# DAC.net
KiCad netlist of a schematic drawn in Altium Designer
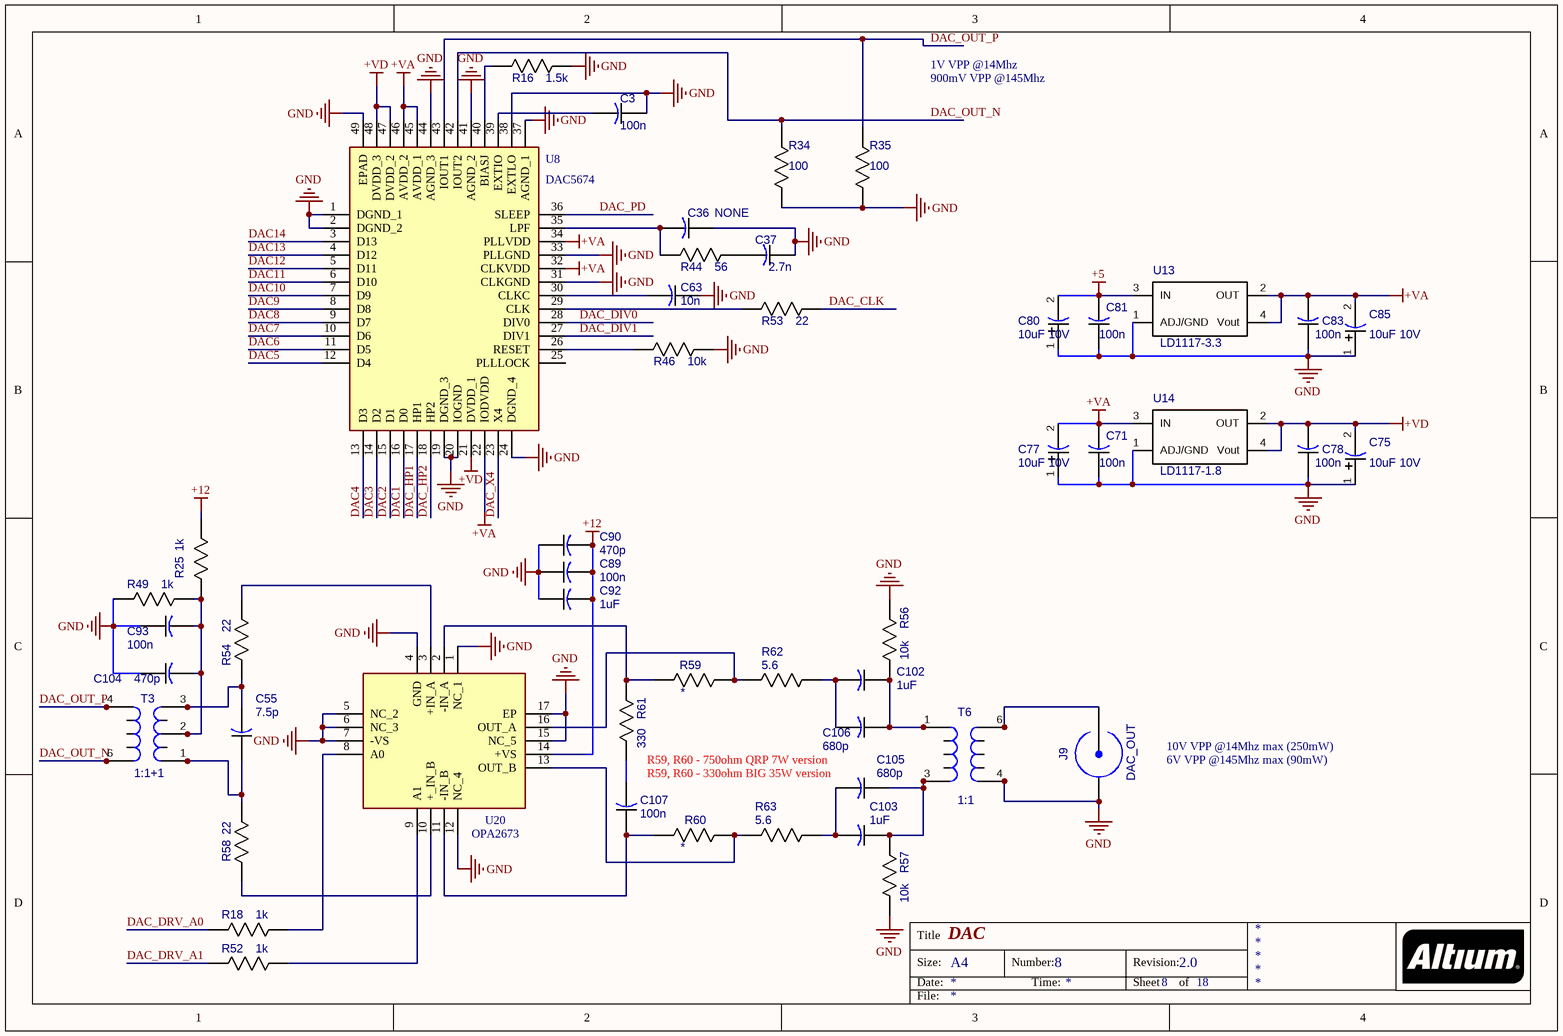
[diagram p0: DAC.SchDoc]

(export (version "E")
  (design (tool "Eeschema 10.0.6"))
  (components
    (comp (ref "C3")
      (value "100n")
      (footprint "CAP_0805")
      (description "CAP_0805")
      (libsource (lib "*") (part "CAP_0805"))
    )
    (comp (ref "C36")
      (value "NONE")
      (footprint "CAP_0805")
      (description "CAP_0805")
      (libsource (lib "*") (part "CAP_0805"))
    )
    (comp (ref "C37")
      (value "2.7n")
      (footprint "CAP_0805")
      (description "CAP_0805")
      (libsource (lib "*") (part "CAP_0805"))
    )
    (comp (ref "C55")
      (value "7.5p")
      (footprint "CAP_0805")
      (description "CAP_0805")
      (libsource (lib "*") (part "CAP_0805"))
    )
    (comp (ref "C63")
      (value "10n")
      (footprint "CAP_0805")
      (description "CAP_0805")
      (libsource (lib "*") (part "CAP_0805"))
    )
    (comp (ref "C71")
      (value "100n")
      (footprint "CAP_0805")
      (description "CAP_0805")
      (libsource (lib "*") (part "CAP_0805"))
    )
    (comp (ref "C75")
      (value "10uF 10V")
      (footprint "CAPAE_4.3x4.3h5.4")
      (description "CAPAE_4.3x4.3h5.4")
      (libsource (lib "MOTHERBOARD") (part "CAPAE_4.3x4.3h5.4"))
    )
    (comp (ref "C77")
      (value "10uF 10V")
      (footprint "CAPAE_4.3x4.3h5.4")
      (description "CAPAE_4.3x4.3h5.4")
      (libsource (lib "MOTHERBOARD") (part "CAPAE_4.3x4.3h5.4"))
    )
    (comp (ref "C78")
      (value "100n")
      (footprint "CAP_0805")
      (description "CAP_0805")
      (libsource (lib "*") (part "CAP_0805"))
    )
    (comp (ref "C80")
      (value "10uF 10V")
      (footprint "CAPAE_4.3x4.3h5.4")
      (description "CAPAE_4.3x4.3h5.4")
      (libsource (lib "MOTHERBOARD") (part "CAPAE_4.3x4.3h5.4"))
    )
    (comp (ref "C81")
      (value "100n")
      (footprint "CAP_0805")
      (description "CAP_0805")
      (libsource (lib "*") (part "CAP_0805"))
    )
    (comp (ref "C83")
      (value "100n")
      (footprint "CAP_0805")
      (description "CAP_0805")
      (libsource (lib "*") (part "CAP_0805"))
    )
    (comp (ref "C85")
      (value "10uF 10V")
      (footprint "CAPAE_4.3x4.3h5.4")
      (description "CAPAE_4.3x4.3h5.4")
      (libsource (lib "MOTHERBOARD") (part "CAPAE_4.3x4.3h5.4"))
    )
    (comp (ref "C89")
      (value "100n")
      (footprint "CAP_0805")
      (description "CAP_0805")
      (libsource (lib "*") (part "CAP_0805"))
    )
    (comp (ref "C90")
      (value "470p")
      (footprint "CAP_0805")
      (description "CAP_0805")
      (libsource (lib "*") (part "CAP_0805"))
    )
    (comp (ref "C92")
      (value "1uF")
      (footprint "CAP_0805")
      (description "CAP_0805")
      (libsource (lib "*") (part "CAP_0805"))
    )
    (comp (ref "C93")
      (value "100n")
      (footprint "CAP_0805")
      (description "CAP_0805")
      (libsource (lib "*") (part "CAP_0805"))
    )
    (comp (ref "C102")
      (value "1uF")
      (footprint "CAP_1206")
      (description "CAP_1206")
      (libsource (lib "*") (part "CAP_1206"))
    )
    (comp (ref "C103")
      (value "1uF")
      (footprint "CAP_1206")
      (description "CAP_1206")
      (libsource (lib "*") (part "CAP_1206"))
    )
    (comp (ref "C104")
      (value "470p")
      (footprint "CAP_0805")
      (description "CAP_0805")
      (libsource (lib "*") (part "CAP_0805"))
    )
    (comp (ref "C105")
      (value "680p")
      (footprint "CAP_1206")
      (description "CAP_1206")
      (libsource (lib "*") (part "CAP_1206"))
    )
    (comp (ref "C106")
      (value "680p")
      (footprint "CAP_1206")
      (description "CAP_1206")
      (libsource (lib "*") (part "CAP_1206"))
    )
    (comp (ref "C107")
      (value "100n")
      (footprint "CAP_0805")
      (description "CAP_0805")
      (libsource (lib "*") (part "CAP_0805"))
    )
    (comp (ref "J9")
      (value "DAC_OUT")
      (footprint "31-5431")
      (description "SMA")
      (libsource (lib "RF-UNIT_1") (part "31-5431"))
    )
    (comp (ref "R16")
      (value "1.5k")
      (footprint "RES_0805")
      (description "RES_0805")
      (libsource (lib "*") (part "RES_0805"))
    )
    (comp (ref "R18")
      (value "1k")
      (footprint "RES_0805")
      (description "RES_0805")
      (libsource (lib "*") (part "RES_0805"))
    )
    (comp (ref "R25")
      (value "1k")
      (footprint "RES_0805")
      (description "RES_0805")
      (libsource (lib "*") (part "RES_0805"))
    )
    (comp (ref "R34")
      (value "100")
      (footprint "RES_0805")
      (description "RES_0805")
      (libsource (lib "*") (part "RES_0805"))
    )
    (comp (ref "R35")
      (value "100")
      (footprint "RES_0805")
      (description "RES_0805")
      (libsource (lib "*") (part "RES_0805"))
    )
    (comp (ref "R44")
      (value "56")
      (footprint "RES_0805")
      (description "RES_0805")
      (libsource (lib "*") (part "RES_0805"))
    )
    (comp (ref "R46")
      (value "10k")
      (footprint "RES_0805")
      (description "RES_0805")
      (libsource (lib "*") (part "RES_0805"))
    )
    (comp (ref "R49")
      (value "1k")
      (footprint "RES_0805")
      (description "RES_0805")
      (libsource (lib "*") (part "RES_0805"))
    )
    (comp (ref "R52")
      (value "1k")
      (footprint "RES_0805")
      (description "RES_0805")
      (libsource (lib "*") (part "RES_0805"))
    )
    (comp (ref "R53")
      (value "22")
      (footprint "RES_0805")
      (description "RES_0805")
      (libsource (lib "*") (part "RES_0805"))
    )
    (comp (ref "R54")
      (value "22")
      (footprint "RES_0805")
      (description "RES_0805")
      (libsource (lib "*") (part "RES_0805"))
    )
    (comp (ref "R56")
      (value "10k")
      (footprint "RES_0805")
      (description "RES_0805")
      (libsource (lib "*") (part "RES_0805"))
    )
    (comp (ref "R57")
      (value "10k")
      (footprint "RES_0805")
      (description "RES_0805")
      (libsource (lib "*") (part "RES_0805"))
    )
    (comp (ref "R58")
      (value "22")
      (footprint "RES_0805")
      (description "RES_0805")
      (libsource (lib "*") (part "RES_0805"))
    )
    (comp (ref "R59")
      (value "*")
      (footprint "RES_0805")
      (description "RES_0805")
      (libsource (lib "*") (part "RES_0805"))
    )
    (comp (ref "R60")
      (value "*")
      (footprint "RES_0805")
      (description "RES_0805")
      (libsource (lib "*") (part "RES_0805"))
    )
    (comp (ref "R61")
      (value "330")
      (footprint "RES_0805")
      (description "RES_0805")
      (libsource (lib "*") (part "RES_0805"))
    )
    (comp (ref "R62")
      (value "5.6")
      (footprint "RES_1206")
      (description "RES_1206")
      (libsource (lib "*") (part "RES_1206"))
    )
    (comp (ref "R63")
      (value "5.6")
      (footprint "RES_1206")
      (description "RES_1206")
      (libsource (lib "*") (part "RES_1206"))
    )
    (comp (ref "T3")
      (value "1:1+1")
      (footprint "TRANSF_ACORE2")
      (description "Transformer")
      (libsource (lib "MOTHERBOARD_1") (part "TRANSF_ACORE2"))
    )
    (comp (ref "T6")
      (value "1:1")
      (footprint "TRANSF_ACORE")
      (description "Transformer")
      (libsource (lib "MOTHERBOARD_1") (part "TRANSF_ACORE"))
    )
    (comp (ref "U8")
      (value "DAC5674")
      (footprint "SamacSys:QFP50P900X900X100-49N")
      (description "Integrated Circuit")
      (fields (field (name "MANUFACTURER_PART_NUMBER") "DAC5674IPHP"))
      (libsource (lib "*") (part "DAC5674IPHP"))
    )
    (comp (ref "U13")
      (value "LD1117-3.3")
      (footprint "LT1117CST-3.3")
      (description "LT1117CST-3.3")
      (fields (field (name "Comment") "1117-3.3"))
      (libsource (lib "*") (part "LT1117CST-3.3"))
    )
    (comp (ref "U14")
      (value "LD1117-1.8")
      (footprint "LT1117CST-3.3")
      (description "LT1117CST-1.8")
      (fields (field (name "Comment") "1117-1.8"))
      (libsource (lib "*") (part "LT1117CST-3.3"))
    )
    (comp (ref "U20")
      (value "OPA2673")
      (footprint "SamacSys:QFN65P400X400X100-17N-D")
      (description "Integrated Circuit")
      (fields
        (field (name "MANUFACTURER_PART_NUMBER") "OPA2673IRGVT")
        (field (name "MOUSER PART NUMBER") "595-OPA2673IRGVT")
      )
      (libsource (lib "*") (part "OPA2673IRGVT"))
    )
  )
  (nets
    (net (code "1") (name "+5") (class "Default")
      (node (ref "C80") (pin "2") (pinfunction "MINUS_2") (pintype "passive"))
      (node (ref "C81") (pin "2") (pinfunction "2_2") (pintype "passive"))
      (node (ref "U13") (pin "3") (pinfunction "IN_3") (pintype "passive"))
    )
    (net (code "2") (name "+12") (class "Default")
      (node (ref "C89") (pin "2") (pinfunction "2_2") (pintype "passive"))
      (node (ref "C90") (pin "2") (pinfunction "2_2") (pintype "passive"))
      (node (ref "C92") (pin "2") (pinfunction "2_2") (pintype "passive"))
      (node (ref "R25") (pin "2") (pinfunction "2_2") (pintype "passive"))
      (node (ref "U20") (pin "14") (pinfunction "+VS_14") (pintype "passive"))
    )
    (net (code "3") (name "+VA") (class "Default")
      (node (ref "C71") (pin "2") (pinfunction "2_2") (pintype "passive"))
      (node (ref "C77") (pin "2") (pinfunction "MINUS_2") (pintype "passive"))
      (node (ref "C83") (pin "2") (pinfunction "2_2") (pintype "passive"))
      (node (ref "C85") (pin "2") (pinfunction "MINUS_2") (pintype "passive"))
      (node (ref "U13") (pin "2") (pinfunction "OUT_2") (pintype "passive"))
      (node (ref "U13") (pin "4") (pinfunction "Vout_4") (pintype "passive"))
      (node (ref "U14") (pin "3") (pinfunction "IN_3") (pintype "passive"))
      (node (ref "U8") (pin "22") (pinfunction "IODVDD_22") (pintype "passive"))
      (node (ref "U8") (pin "32") (pinfunction "CLKVDD_32") (pintype "passive"))
      (node (ref "U8") (pin "34") (pinfunction "PLLVDD_34") (pintype "passive"))
      (node (ref "U8") (pin "45") (pinfunction "AVDD_1_45") (pintype "passive"))
      (node (ref "U8") (pin "46") (pinfunction "AVDD_2_46") (pintype "passive"))
    )
    (net (code "4") (name "+VD") (class "Default")
      (node (ref "C75") (pin "2") (pinfunction "MINUS_2") (pintype "passive"))
      (node (ref "C78") (pin "2") (pinfunction "2_2") (pintype "passive"))
      (node (ref "U14") (pin "2") (pinfunction "OUT_2") (pintype "passive"))
      (node (ref "U14") (pin "4") (pinfunction "Vout_4") (pintype "passive"))
      (node (ref "U8") (pin "21") (pinfunction "DVDD_1_21") (pintype "passive"))
      (node (ref "U8") (pin "47") (pinfunction "DVDD_2_47") (pintype "passive"))
      (node (ref "U8") (pin "48") (pinfunction "DVDD_3_48") (pintype "passive"))
    )
    (net (code "5") (name "/DAC1") (class "Default")
      (node (ref "U8") (pin "16") (pinfunction "D0_16") (pintype "passive"))
    )
    (net (code "6") (name "/DAC2") (class "Default")
      (node (ref "U8") (pin "15") (pinfunction "D1_15") (pintype "passive"))
    )
    (net (code "7") (name "/DAC3") (class "Default")
      (node (ref "U8") (pin "14") (pinfunction "D2_14") (pintype "passive"))
    )
    (net (code "8") (name "/DAC4") (class "Default")
      (node (ref "U8") (pin "13") (pinfunction "D3_13") (pintype "passive"))
    )
    (net (code "9") (name "/DAC5") (class "Default")
      (node (ref "U8") (pin "12") (pinfunction "D4_12") (pintype "passive"))
    )
    (net (code "10") (name "/DAC6") (class "Default")
      (node (ref "U8") (pin "11") (pinfunction "D5_11") (pintype "passive"))
    )
    (net (code "11") (name "/DAC7") (class "Default")
      (node (ref "U8") (pin "10") (pinfunction "D6_10") (pintype "passive"))
    )
    (net (code "12") (name "/DAC8") (class "Default")
      (node (ref "U8") (pin "9") (pinfunction "D7_9") (pintype "passive"))
    )
    (net (code "13") (name "/DAC9") (class "Default")
      (node (ref "U8") (pin "8") (pinfunction "D8_8") (pintype "passive"))
    )
    (net (code "14") (name "/DAC10") (class "Default")
      (node (ref "U8") (pin "7") (pinfunction "D9_7") (pintype "passive"))
    )
    (net (code "15") (name "/DAC11") (class "Default")
      (node (ref "U8") (pin "6") (pinfunction "D10_6") (pintype "passive"))
    )
    (net (code "16") (name "/DAC12") (class "Default")
      (node (ref "U8") (pin "5") (pinfunction "D11_5") (pintype "passive"))
    )
    (net (code "17") (name "/DAC13") (class "Default")
      (node (ref "U8") (pin "4") (pinfunction "D12_4") (pintype "passive"))
    )
    (net (code "18") (name "/DAC14") (class "Default")
      (node (ref "U8") (pin "3") (pinfunction "D13_3") (pintype "passive"))
    )
    (net (code "19") (name "/DAC_CLK") (class "Default")
      (node (ref "R53") (pin "1") (pinfunction "1_1") (pintype "passive"))
    )
    (net (code "20") (name "/DAC_DIV0") (class "Default")
      (node (ref "U8") (pin "28") (pinfunction "DIV0_28") (pintype "passive"))
    )
    (net (code "21") (name "/DAC_DIV1") (class "Default")
      (node (ref "U8") (pin "27") (pinfunction "DIV1_27") (pintype "passive"))
    )
    (net (code "22") (name "/DAC_DRV_A0") (class "Default")
      (node (ref "R18") (pin "1") (pinfunction "1_1") (pintype "passive"))
    )
    (net (code "23") (name "/DAC_DRV_A1") (class "Default")
      (node (ref "R52") (pin "1") (pinfunction "1_1") (pintype "passive"))
    )
    (net (code "24") (name "/DAC_HP1") (class "Default")
      (node (ref "U8") (pin "17") (pinfunction "HP1_17") (pintype "passive"))
    )
    (net (code "25") (name "/DAC_HP2") (class "Default")
      (node (ref "U8") (pin "18") (pinfunction "HP2_18") (pintype "passive"))
    )
    (net (code "26") (name "/DAC_OUT_N") (class "Default")
      (node (ref "R34") (pin "2") (pinfunction "2_2") (pintype "passive"))
      (node (ref "T3") (pin "10") (pinfunction "0_10") (pintype "passive"))
      (node (ref "T3") (pin "6") (pinfunction "P2_6") (pintype "passive"))
      (node (ref "U8") (pin "42") (pinfunction "IOUT2_42") (pintype "passive"))
    )
    (net (code "27") (name "/DAC_OUT_P") (class "Default")
      (node (ref "R35") (pin "2") (pinfunction "2_2") (pintype "passive"))
      (node (ref "T3") (pin "11") (pinfunction "0_11") (pintype "passive"))
      (node (ref "T3") (pin "4") (pinfunction "P1_4") (pintype "passive"))
      (node (ref "U8") (pin "43") (pinfunction "IOUT1_43") (pintype "passive"))
    )
    (net (code "28") (name "/DAC_PD") (class "Default")
      (node (ref "U8") (pin "36") (pinfunction "SLEEP_36") (pintype "passive"))
    )
    (net (code "29") (name "/DAC_X4") (class "Default")
      (node (ref "U8") (pin "23") (pinfunction "X4_23") (pintype "passive"))
    )
    (net (code "30") (name "GND") (class "Default")
      (node (ref "C104") (pin "1") (pinfunction "1_1") (pintype "passive"))
      (node (ref "C3") (pin "1") (pinfunction "1_1") (pintype "passive"))
      (node (ref "C36") (pin "1") (pinfunction "1_1") (pintype "passive"))
      (node (ref "C37") (pin "1") (pinfunction "1_1") (pintype "passive"))
      (node (ref "C63") (pin "1") (pinfunction "1_1") (pintype "passive"))
      (node (ref "C71") (pin "1") (pinfunction "1_1") (pintype "passive"))
      (node (ref "C75") (pin "1") (pinfunction "PLUS_1") (pintype "passive"))
      (node (ref "C77") (pin "1") (pinfunction "PLUS_1") (pintype "passive"))
      (node (ref "C78") (pin "1") (pinfunction "1_1") (pintype "passive"))
      (node (ref "C80") (pin "1") (pinfunction "PLUS_1") (pintype "passive"))
      (node (ref "C81") (pin "1") (pinfunction "1_1") (pintype "passive"))
      (node (ref "C83") (pin "1") (pinfunction "1_1") (pintype "passive"))
      (node (ref "C85") (pin "1") (pinfunction "PLUS_1") (pintype "passive"))
      (node (ref "C89") (pin "1") (pinfunction "1_1") (pintype "passive"))
      (node (ref "C90") (pin "1") (pinfunction "1_1") (pintype "passive"))
      (node (ref "C92") (pin "1") (pinfunction "1_1") (pintype "passive"))
      (node (ref "C93") (pin "1") (pinfunction "1_1") (pintype "passive"))
      (node (ref "J9") (pin "1") (pinfunction "GND_1") (pintype "passive"))
      (node (ref "J9") (pin "2") (pinfunction "GND_2") (pintype "passive"))
      (node (ref "J9") (pin "3") (pinfunction "GND_3") (pintype "passive"))
      (node (ref "J9") (pin "4") (pinfunction "GND_4") (pintype "passive"))
      (node (ref "R16") (pin "1") (pinfunction "1_1") (pintype "passive"))
      (node (ref "R34") (pin "1") (pinfunction "1_1") (pintype "passive"))
      (node (ref "R35") (pin "1") (pinfunction "1_1") (pintype "passive"))
      (node (ref "R46") (pin "1") (pinfunction "1_1") (pintype "passive"))
      (node (ref "R49") (pin "2") (pinfunction "2_2") (pintype "passive"))
      (node (ref "R56") (pin "1") (pinfunction "1_1") (pintype "passive"))
      (node (ref "R57") (pin "2") (pinfunction "2_2") (pintype "passive"))
      (node (ref "T6") (pin "11") (pinfunction "0_11") (pintype "passive"))
      (node (ref "T6") (pin "4") (pinfunction "S2_4") (pintype "passive"))
      (node (ref "U13") (pin "1") (pinfunction "ADJ/GND_1") (pintype "passive"))
      (node (ref "U14") (pin "1") (pinfunction "ADJ/GND_1") (pintype "passive"))
      (node (ref "U20") (pin "1") (pinfunction "NC_1_1") (pintype "passive"))
      (node (ref "U20") (pin "12") (pinfunction "NC_4_12") (pintype "passive"))
      (node (ref "U20") (pin "15") (pinfunction "NC_5_15") (pintype "passive"))
      (node (ref "U20") (pin "17") (pinfunction "EP_17") (pintype "passive"))
      (node (ref "U20") (pin "4") (pinfunction "GND_4") (pintype "passive"))
      (node (ref "U20") (pin "5") (pinfunction "NC_2_5") (pintype "passive"))
      (node (ref "U20") (pin "6") (pinfunction "NC_3_6") (pintype "passive"))
      (node (ref "U20") (pin "7") (pinfunction "-VS_7") (pintype "passive"))
      (node (ref "U8") (pin "1") (pinfunction "DGND_1_1") (pintype "passive"))
      (node (ref "U8") (pin "19") (pinfunction "DGND_3_19") (pintype "passive"))
      (node (ref "U8") (pin "2") (pinfunction "DGND_2_2") (pintype "passive"))
      (node (ref "U8") (pin "20") (pinfunction "IOGND_20") (pintype "passive"))
      (node (ref "U8") (pin "24") (pinfunction "DGND_4_24") (pintype "passive"))
      (node (ref "U8") (pin "31") (pinfunction "CLKGND_31") (pintype "passive"))
      (node (ref "U8") (pin "33") (pinfunction "PLLGND_33") (pintype "passive"))
      (node (ref "U8") (pin "37") (pinfunction "AGND_1_37") (pintype "passive"))
      (node (ref "U8") (pin "38") (pinfunction "EXTLO_38") (pintype "passive"))
      (node (ref "U8") (pin "41") (pinfunction "AGND_2_41") (pintype "passive"))
      (node (ref "U8") (pin "44") (pinfunction "AGND_3_44") (pintype "passive"))
      (node (ref "U8") (pin "49") (pinfunction "EPAD_49") (pintype "passive"))
    )
    (net (code "31") (name "Net-(C37-Pad2)") (class "Default")
      (node (ref "C37") (pin "2") (pinfunction "2_2") (pintype "passive"))
      (node (ref "R44") (pin "1") (pinfunction "1_1") (pintype "passive"))
    )
    (net (code "32") (name "Net-(C102-Pad2)") (class "Default")
      (node (ref "C102") (pin "2") (pinfunction "2_2") (pintype "passive"))
      (node (ref "C106") (pin "2") (pinfunction "2_2") (pintype "passive"))
      (node (ref "R62") (pin "1") (pinfunction "1_1") (pintype "passive"))
    )
    (net (code "33") (name "Net-(C103-Pad2)") (class "Default")
      (node (ref "C103") (pin "2") (pinfunction "2_2") (pintype "passive"))
      (node (ref "C105") (pin "2") (pinfunction "2_2") (pintype "passive"))
      (node (ref "R63") (pin "1") (pinfunction "1_1") (pintype "passive"))
    )
    (net (code "34") (name "Net-(C107-Pad2)") (class "Default")
      (node (ref "C107") (pin "2") (pinfunction "2_2") (pintype "passive"))
      (node (ref "R61") (pin "2") (pinfunction "2_2") (pintype "passive"))
    )
    (net (code "35") (name "Net-(J9-CON)") (class "Default")
      (node (ref "J9") (pin "5") (pinfunction "CON_5") (pintype "passive"))
      (node (ref "T6") (pin "10") (pinfunction "0_10") (pintype "passive"))
      (node (ref "T6") (pin "6") (pinfunction "S1_6") (pintype "passive"))
    )
    (net (code "36") (name "Net-(T3-S1)") (class "Default")
      (node (ref "C55") (pin "2") (pinfunction "2_2") (pintype "passive"))
      (node (ref "R54") (pin "1") (pinfunction "1_1") (pintype "passive"))
      (node (ref "T3") (pin "3") (pinfunction "S1_3") (pintype "passive"))
      (node (ref "T3") (pin "9") (pinfunction "0_9") (pintype "passive"))
    )
    (net (code "37") (name "Net-(T3-S2)") (class "Default")
      (node (ref "C104") (pin "2") (pinfunction "2_2") (pintype "passive"))
      (node (ref "C93") (pin "2") (pinfunction "2_2") (pintype "passive"))
      (node (ref "R25") (pin "1") (pinfunction "1_1") (pintype "passive"))
      (node (ref "R49") (pin "1") (pinfunction "1_1") (pintype "passive"))
      (node (ref "T3") (pin "2") (pinfunction "S2_2") (pintype "passive"))
      (node (ref "T3") (pin "8") (pinfunction "0_8") (pintype "passive"))
    )
    (net (code "38") (name "Net-(T3-S3)") (class "Default")
      (node (ref "C55") (pin "1") (pinfunction "1_1") (pintype "passive"))
      (node (ref "R58") (pin "2") (pinfunction "2_2") (pintype "passive"))
      (node (ref "T3") (pin "1") (pinfunction "S3_1") (pintype "passive"))
      (node (ref "T3") (pin "7") (pinfunction "0_7") (pintype "passive"))
    )
    (net (code "39") (name "Net-(T6-P1)") (class "Default")
      (node (ref "C102") (pin "1") (pinfunction "1_1") (pintype "passive"))
      (node (ref "C106") (pin "1") (pinfunction "1_1") (pintype "passive"))
      (node (ref "R56") (pin "2") (pinfunction "2_2") (pintype "passive"))
      (node (ref "T6") (pin "1") (pinfunction "P1_1") (pintype "passive"))
      (node (ref "T6") (pin "7") (pinfunction "0_7") (pintype "passive"))
    )
    (net (code "40") (name "Net-(T6-P2)") (class "Default")
      (node (ref "C103") (pin "1") (pinfunction "1_1") (pintype "passive"))
      (node (ref "C105") (pin "1") (pinfunction "1_1") (pintype "passive"))
      (node (ref "R57") (pin "1") (pinfunction "1_1") (pintype "passive"))
      (node (ref "T6") (pin "3") (pinfunction "P2_3") (pintype "passive"))
      (node (ref "T6") (pin "9") (pinfunction "0_9") (pintype "passive"))
    )
    (net (code "41") (name "Net-(U8-BIASJ)") (class "Default")
      (node (ref "R16") (pin "2") (pinfunction "2_2") (pintype "passive"))
      (node (ref "U8") (pin "40") (pinfunction "BIASJ_40") (pintype "passive"))
    )
    (net (code "42") (name "Net-(U8-CLK)") (class "Default")
      (node (ref "R53") (pin "2") (pinfunction "2_2") (pintype "passive"))
      (node (ref "U8") (pin "29") (pinfunction "CLK_29") (pintype "passive"))
    )
    (net (code "43") (name "Net-(U8-CLKC)") (class "Default")
      (node (ref "C63") (pin "2") (pinfunction "2_2") (pintype "passive"))
      (node (ref "U8") (pin "30") (pinfunction "CLKC_30") (pintype "passive"))
    )
    (net (code "44") (name "Net-(U8-EXTIO)") (class "Default")
      (node (ref "C3") (pin "2") (pinfunction "2_2") (pintype "passive"))
      (node (ref "U8") (pin "39") (pinfunction "EXTIO_39") (pintype "passive"))
    )
    (net (code "45") (name "Net-(U8-LPF)") (class "Default")
      (node (ref "C36") (pin "2") (pinfunction "2_2") (pintype "passive"))
      (node (ref "R44") (pin "2") (pinfunction "2_2") (pintype "passive"))
      (node (ref "U8") (pin "35") (pinfunction "LPF_35") (pintype "passive"))
    )
    (net (code "46") (name "Net-(U8-RESET)") (class "Default")
      (node (ref "R46") (pin "2") (pinfunction "2_2") (pintype "passive"))
      (node (ref "U8") (pin "26") (pinfunction "RESET_26") (pintype "passive"))
    )
    (net (code "47") (name "Net-(U20-+IN_A)") (class "Default")
      (node (ref "R54") (pin "2") (pinfunction "2_2") (pintype "passive"))
      (node (ref "U20") (pin "3") (pinfunction "+IN_A_3") (pintype "passive"))
    )
    (net (code "48") (name "Net-(U20-+_IN_B)") (class "Default")
      (node (ref "R58") (pin "1") (pinfunction "1_1") (pintype "passive"))
      (node (ref "U20") (pin "10") (pinfunction "+_IN_B_10") (pintype "passive"))
    )
    (net (code "49") (name "Net-(U20--IN_A)") (class "Default")
      (node (ref "R59") (pin "2") (pinfunction "2_2") (pintype "passive"))
      (node (ref "R61") (pin "1") (pinfunction "1_1") (pintype "passive"))
      (node (ref "U20") (pin "2") (pinfunction "-IN_A_2") (pintype "passive"))
    )
    (net (code "50") (name "Net-(U20--IN_B)") (class "Default")
      (node (ref "C107") (pin "1") (pinfunction "1_1") (pintype "passive"))
      (node (ref "R60") (pin "2") (pinfunction "2_2") (pintype "passive"))
      (node (ref "U20") (pin "11") (pinfunction "-IN_B_11") (pintype "passive"))
    )
    (net (code "51") (name "Net-(U20-A0)") (class "Default")
      (node (ref "R18") (pin "2") (pinfunction "2_2") (pintype "passive"))
      (node (ref "U20") (pin "8") (pinfunction "A0_8") (pintype "passive"))
    )
    (net (code "52") (name "Net-(U20-A1)") (class "Default")
      (node (ref "R52") (pin "2") (pinfunction "2_2") (pintype "passive"))
      (node (ref "U20") (pin "9") (pinfunction "A1_9") (pintype "passive"))
    )
    (net (code "53") (name "Net-(U20-OUT_A)") (class "Default")
      (node (ref "R59") (pin "1") (pinfunction "1_1") (pintype "passive"))
      (node (ref "R62") (pin "2") (pinfunction "2_2") (pintype "passive"))
      (node (ref "U20") (pin "16") (pinfunction "OUT_A_16") (pintype "passive"))
    )
    (net (code "54") (name "Net-(U20-OUT_B)") (class "Default")
      (node (ref "R60") (pin "1") (pinfunction "1_1") (pintype "passive"))
      (node (ref "R63") (pin "2") (pinfunction "2_2") (pintype "passive"))
      (node (ref "U20") (pin "13") (pinfunction "OUT_B_13") (pintype "passive"))
    )
    (net (code "55") (name "unconnected-(T6-0-Pad8)") (class "Default")
      (node (ref "T6") (pin "8") (pinfunction "0_8") (pintype "passive"))
    )
    (net (code "56") (name "unconnected-(U8-PLLLOCK-Pad25)") (class "Default")
      (node (ref "U8") (pin "25") (pinfunction "PLLLOCK_25") (pintype "passive"))
    )
  )
)
